# Fiber_optic_inputs.net
KiCad netlist of a schematic drawn in Altium Designer
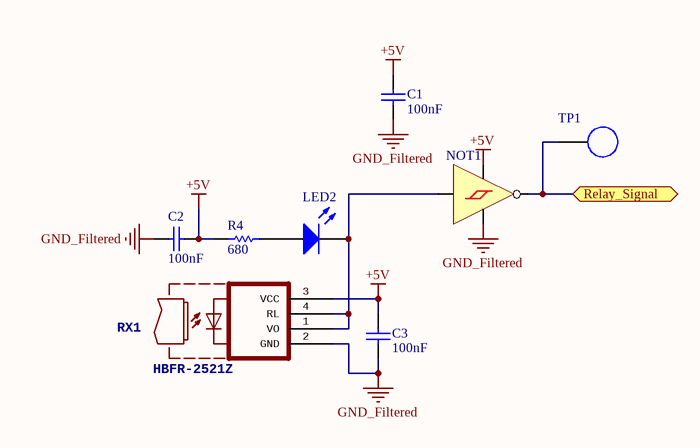
[diagram p0: Fiber optic_inputs.SchDoc]

(export (version "E")
  (design (tool "Eeschema 10.0.6"))
  (components
    (comp (ref "C1")
      (value "100nF")
      (footprint "Footprints_SOC:CAP_0603")
      (description "Capacitor")
      (fields (field (name "PUBLISHER") "Altium Limited"))
      (libsource (lib "Componentes_SOC") (part "Cap"))
    )
    (comp (ref "C2")
      (value "100nF")
      (footprint "Footprints_SOC:CAP_0603")
      (description "Capacitor")
      (fields (field (name "PUBLISHER") "Altium Limited"))
      (libsource (lib "Componentes_SOC") (part "Cap"))
    )
    (comp (ref "C3")
      (value "100nF")
      (footprint "Footprints_SOC:CAP_0603")
      (description "Capacitor")
      (fields (field (name "PUBLISHER") "Altium Limited"))
      (libsource (lib "Componentes_SOC") (part "Cap"))
    )
    (comp (ref "LED2")
      (value "LED")
      (footprint "LED_0805_GREEN")
      (description "LED Green")
      (fields (field (name "PUBLISHER") "Altium Limited"))
      (libsource (lib "Componentes_SOC") (part "LED2"))
    )
    (comp (ref "NOT1")
      (value "INV_CMOS")
      (footprint "INV_SN74AHC1G14DBVR")
      (libsource (lib "Componentes_SOC") (part "INV CMOS"))
    )
    (comp (ref "R4")
      (value "680")
      (footprint "RES_0603")
      (description "Resistor")
      (fields (field (name "PUBLISHER") "Altium Limited"))
      (libsource (lib "Componentes_SOC") (part "Res0603"))
    )
    (comp (ref "RX1")
      (value "HBFR-2521Z")
      (footprint "HFBR-15X1V")
      (description "Receptor optico horizontal")
      (libsource (lib "Componentes_SOC") (part "HFBR-2521"))
    )
    (comp (ref "TP1")
      (value "Test Point 0805")
      (footprint "Test Point 0805")
      (description "Surface Mount Test Points")
      (libsource (lib "Componentes_SOC") (part "Test Point 0805"))
    )
  )
  (nets
    (net (code "1") (name "+5V") (class "Default")
      (node (ref "C1") (pin "1") (pinfunction "1_1") (pintype "passive"))
      (node (ref "C2") (pin "2") (pinfunction "2_2") (pintype "passive"))
      (node (ref "C3") (pin "1") (pinfunction "1_1") (pintype "passive"))
      (node (ref "NOT1") (pin "5") (pinfunction "Vcc_5") (pintype "passive"))
      (node (ref "R4") (pin "1") (pinfunction "1_1") (pintype "passive"))
      (node (ref "RX1") (pin "3") (pinfunction "VCC_3") (pintype "power_in"))
    )
    (net (code "2") (name "/Relay_Signal") (class "Default")
      (node (ref "NOT1") (pin "4") (pinfunction "Vcc_4") (pintype "passive"))
      (node (ref "TP1") (pin "1") (pinfunction "TP_1") (pintype "passive"))
    )
    (net (code "3") (name "GND_Filtered") (class "Default")
      (node (ref "C1") (pin "2") (pinfunction "2_2") (pintype "passive"))
      (node (ref "C2") (pin "1") (pinfunction "1_1") (pintype "passive"))
      (node (ref "C3") (pin "2") (pinfunction "2_2") (pintype "passive"))
      (node (ref "NOT1") (pin "3") (pinfunction "GND_3") (pintype "passive"))
      (node (ref "RX1") (pin "2") (pinfunction "GND_2") (pintype "power_in"))
    )
    (net (code "4") (name "Net-(LED2-A)") (class "Default")
      (node (ref "LED2") (pin "1") (pinfunction "A_1") (pintype "passive"))
      (node (ref "R4") (pin "2") (pinfunction "2_2") (pintype "passive"))
    )
    (net (code "5") (name "Net-(LED2-K)") (class "Default")
      (node (ref "LED2") (pin "2") (pinfunction "K_2") (pintype "passive"))
      (node (ref "NOT1") (pin "2") (pinfunction "A_2") (pintype "passive"))
      (node (ref "RX1") (pin "1") (pinfunction "VO_1") (pintype "passive"))
      (node (ref "RX1") (pin "4") (pinfunction "RL_4") (pintype "passive"))
    )
    (net (code "6") (name "unconnected-(NOT1-NC-Pad1)") (class "Default")
      (node (ref "NOT1") (pin "1") (pinfunction "NC_1") (pintype "passive"))
    )
  )
)
